# APM2_Adapter.net
KiCad netlist of a schematic drawn in EAGLE
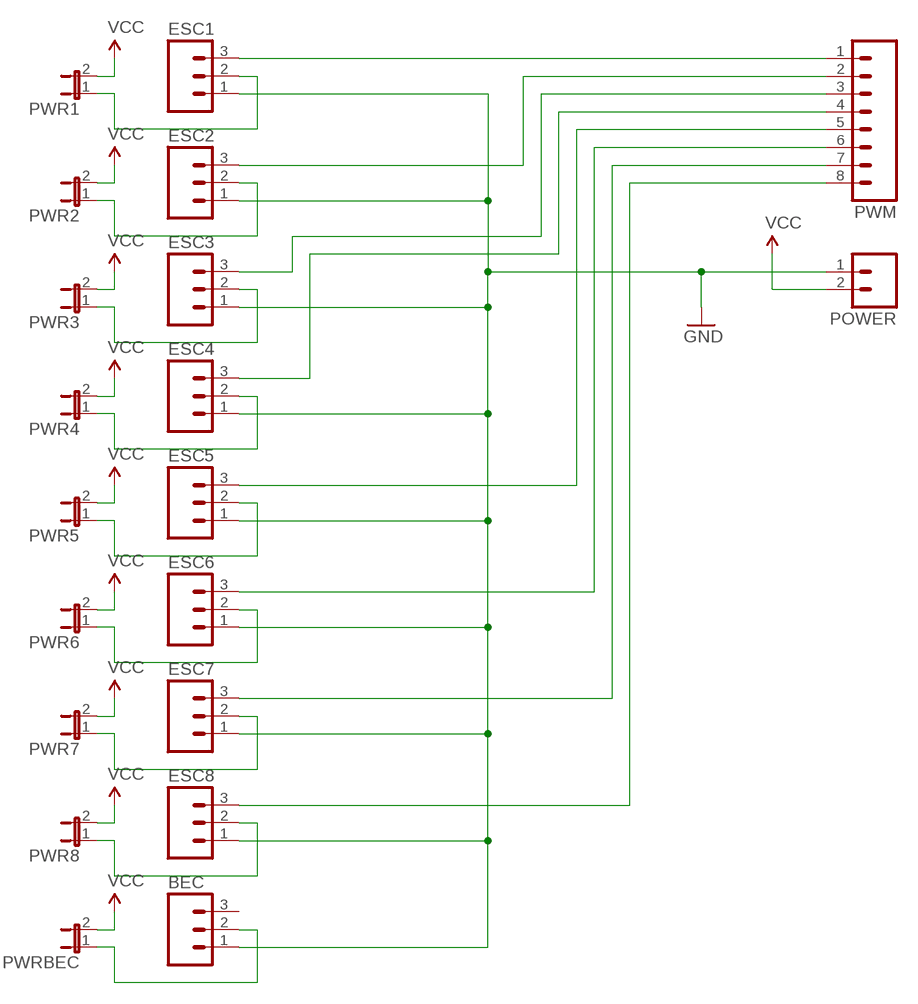
[diagram p0: schematic, sheet 1]

(export (version "E")
  (design (tool "Eeschema 10.0.6"))
  (components
    (comp (ref "BEC")
      (value "M03LOCK")
      (footprint "eagle-import:1X03_LOCK")
      (libsource (lib "eagle-import") (part "M03LOCK"))
    )
    (comp (ref "ESC1")
      (value "M03LOCK")
      (footprint "eagle-import:1X03_LOCK")
      (libsource (lib "eagle-import") (part "M03LOCK"))
    )
    (comp (ref "ESC2")
      (value "M03LOCK")
      (footprint "eagle-import:1X03_LOCK")
      (libsource (lib "eagle-import") (part "M03LOCK"))
    )
    (comp (ref "ESC3")
      (value "M03LOCK")
      (footprint "eagle-import:1X03_LOCK")
      (libsource (lib "eagle-import") (part "M03LOCK"))
    )
    (comp (ref "ESC4")
      (value "M03LOCK")
      (footprint "eagle-import:1X03_LOCK")
      (libsource (lib "eagle-import") (part "M03LOCK"))
    )
    (comp (ref "ESC5")
      (value "M03LOCK")
      (footprint "eagle-import:1X03_LOCK")
      (libsource (lib "eagle-import") (part "M03LOCK"))
    )
    (comp (ref "ESC6")
      (value "M03LOCK")
      (footprint "eagle-import:1X03_LOCK")
      (libsource (lib "eagle-import") (part "M03LOCK"))
    )
    (comp (ref "ESC7")
      (value "M03LOCK")
      (footprint "eagle-import:1X03_LOCK")
      (libsource (lib "eagle-import") (part "M03LOCK"))
    )
    (comp (ref "ESC8")
      (value "M03LOCK")
      (footprint "eagle-import:1X03_LOCK")
      (libsource (lib "eagle-import") (part "M03LOCK"))
    )
    (comp (ref "POWER")
      (value "M02LOCK")
      (footprint "eagle-import:1X02_LOCK")
      (libsource (lib "eagle-import") (part "M02LOCK"))
    )
    (comp (ref "PWM")
      (value "M08LOCK")
      (footprint "eagle-import:1X08_LOCK")
      (libsource (lib "eagle-import") (part "M08LOCK"))
    )
    (comp (ref "PWR1")
      (value "JUMPER-2PTH")
      (footprint "eagle-import:1X02")
      (libsource (lib "eagle-import") (part "JUMPER-2PTH"))
    )
    (comp (ref "PWR2")
      (value "JUMPER-2PTH")
      (footprint "eagle-import:1X02")
      (libsource (lib "eagle-import") (part "JUMPER-2PTH"))
    )
    (comp (ref "PWR3")
      (value "JUMPER-2PTH")
      (footprint "eagle-import:1X02")
      (libsource (lib "eagle-import") (part "JUMPER-2PTH"))
    )
    (comp (ref "PWR4")
      (value "JUMPER-2PTH")
      (footprint "eagle-import:1X02")
      (libsource (lib "eagle-import") (part "JUMPER-2PTH"))
    )
    (comp (ref "PWR5")
      (value "JUMPER-2PTH")
      (footprint "eagle-import:1X02")
      (libsource (lib "eagle-import") (part "JUMPER-2PTH"))
    )
    (comp (ref "PWR6")
      (value "JUMPER-2PTH")
      (footprint "eagle-import:1X02")
      (libsource (lib "eagle-import") (part "JUMPER-2PTH"))
    )
    (comp (ref "PWR7")
      (value "JUMPER-2PTH")
      (footprint "eagle-import:1X02")
      (libsource (lib "eagle-import") (part "JUMPER-2PTH"))
    )
    (comp (ref "PWR8")
      (value "JUMPER-2PTH")
      (footprint "eagle-import:1X02")
      (libsource (lib "eagle-import") (part "JUMPER-2PTH"))
    )
    (comp (ref "PWRBEC")
      (value "JUMPER-2PTH")
      (footprint "eagle-import:1X02")
      (libsource (lib "eagle-import") (part "JUMPER-2PTH"))
    )
  )
  (nets
    (net (code "1") (name "GND") (class "Default")
      (node (ref "BEC") (pin "1") (pinfunction "1_1") (pintype "passive"))
      (node (ref "ESC1") (pin "1") (pinfunction "1_1") (pintype "passive"))
      (node (ref "ESC2") (pin "1") (pinfunction "1_1") (pintype "passive"))
      (node (ref "ESC3") (pin "1") (pinfunction "1_1") (pintype "passive"))
      (node (ref "ESC4") (pin "1") (pinfunction "1_1") (pintype "passive"))
      (node (ref "ESC5") (pin "1") (pinfunction "1_1") (pintype "passive"))
      (node (ref "ESC6") (pin "1") (pinfunction "1_1") (pintype "passive"))
      (node (ref "ESC7") (pin "1") (pinfunction "1_1") (pintype "passive"))
      (node (ref "ESC8") (pin "1") (pinfunction "1_1") (pintype "passive"))
      (node (ref "POWER") (pin "1") (pinfunction "1_1") (pintype "passive"))
    )
    (net (code "2") (name "Net-(BEC-Pad2)") (class "Default")
      (node (ref "BEC") (pin "2") (pinfunction "2_2") (pintype "passive"))
      (node (ref "PWRBEC") (pin "1") (pinfunction "1_1") (pintype "passive"))
    )
    (net (code "3") (name "Net-(ESC1-Pad2)") (class "Default")
      (node (ref "ESC1") (pin "2") (pinfunction "2_2") (pintype "passive"))
      (node (ref "PWR1") (pin "1") (pinfunction "1_1") (pintype "passive"))
    )
    (net (code "4") (name "Net-(ESC1-Pad3)") (class "Default")
      (node (ref "ESC1") (pin "3") (pinfunction "3_3") (pintype "passive"))
      (node (ref "PWM") (pin "1") (pinfunction "1_1") (pintype "passive"))
    )
    (net (code "5") (name "Net-(ESC2-Pad2)") (class "Default")
      (node (ref "ESC2") (pin "2") (pinfunction "2_2") (pintype "passive"))
      (node (ref "PWR2") (pin "1") (pinfunction "1_1") (pintype "passive"))
    )
    (net (code "6") (name "Net-(ESC2-Pad3)") (class "Default")
      (node (ref "ESC2") (pin "3") (pinfunction "3_3") (pintype "passive"))
      (node (ref "PWM") (pin "2") (pinfunction "2_2") (pintype "passive"))
    )
    (net (code "7") (name "Net-(ESC3-Pad2)") (class "Default")
      (node (ref "ESC3") (pin "2") (pinfunction "2_2") (pintype "passive"))
      (node (ref "PWR3") (pin "1") (pinfunction "1_1") (pintype "passive"))
    )
    (net (code "8") (name "Net-(ESC3-Pad3)") (class "Default")
      (node (ref "ESC3") (pin "3") (pinfunction "3_3") (pintype "passive"))
      (node (ref "PWM") (pin "3") (pinfunction "3_3") (pintype "passive"))
    )
    (net (code "9") (name "Net-(ESC4-Pad2)") (class "Default")
      (node (ref "ESC4") (pin "2") (pinfunction "2_2") (pintype "passive"))
      (node (ref "PWR4") (pin "1") (pinfunction "1_1") (pintype "passive"))
    )
    (net (code "10") (name "Net-(ESC4-Pad3)") (class "Default")
      (node (ref "ESC4") (pin "3") (pinfunction "3_3") (pintype "passive"))
      (node (ref "PWM") (pin "4") (pinfunction "4_4") (pintype "passive"))
    )
    (net (code "11") (name "Net-(ESC5-Pad2)") (class "Default")
      (node (ref "ESC5") (pin "2") (pinfunction "2_2") (pintype "passive"))
      (node (ref "PWR5") (pin "1") (pinfunction "1_1") (pintype "passive"))
    )
    (net (code "12") (name "Net-(ESC5-Pad3)") (class "Default")
      (node (ref "ESC5") (pin "3") (pinfunction "3_3") (pintype "passive"))
      (node (ref "PWM") (pin "5") (pinfunction "5_5") (pintype "passive"))
    )
    (net (code "13") (name "Net-(ESC6-Pad2)") (class "Default")
      (node (ref "ESC6") (pin "2") (pinfunction "2_2") (pintype "passive"))
      (node (ref "PWR6") (pin "1") (pinfunction "1_1") (pintype "passive"))
    )
    (net (code "14") (name "Net-(ESC6-Pad3)") (class "Default")
      (node (ref "ESC6") (pin "3") (pinfunction "3_3") (pintype "passive"))
      (node (ref "PWM") (pin "6") (pinfunction "6_6") (pintype "passive"))
    )
    (net (code "15") (name "Net-(ESC7-Pad2)") (class "Default")
      (node (ref "ESC7") (pin "2") (pinfunction "2_2") (pintype "passive"))
      (node (ref "PWR7") (pin "1") (pinfunction "1_1") (pintype "passive"))
    )
    (net (code "16") (name "Net-(ESC7-Pad3)") (class "Default")
      (node (ref "ESC7") (pin "3") (pinfunction "3_3") (pintype "passive"))
      (node (ref "PWM") (pin "7") (pinfunction "7_7") (pintype "passive"))
    )
    (net (code "17") (name "Net-(ESC8-Pad2)") (class "Default")
      (node (ref "ESC8") (pin "2") (pinfunction "2_2") (pintype "passive"))
      (node (ref "PWR8") (pin "1") (pinfunction "1_1") (pintype "passive"))
    )
    (net (code "18") (name "Net-(ESC8-Pad3)") (class "Default")
      (node (ref "ESC8") (pin "3") (pinfunction "3_3") (pintype "passive"))
      (node (ref "PWM") (pin "8") (pinfunction "8_8") (pintype "passive"))
    )
    (net (code "19") (name "VCC") (class "Default")
      (node (ref "POWER") (pin "2") (pinfunction "2_2") (pintype "passive"))
      (node (ref "PWR1") (pin "2") (pinfunction "2_2") (pintype "passive"))
      (node (ref "PWR2") (pin "2") (pinfunction "2_2") (pintype "passive"))
      (node (ref "PWR3") (pin "2") (pinfunction "2_2") (pintype "passive"))
      (node (ref "PWR4") (pin "2") (pinfunction "2_2") (pintype "passive"))
      (node (ref "PWR5") (pin "2") (pinfunction "2_2") (pintype "passive"))
      (node (ref "PWR6") (pin "2") (pinfunction "2_2") (pintype "passive"))
      (node (ref "PWR7") (pin "2") (pinfunction "2_2") (pintype "passive"))
      (node (ref "PWR8") (pin "2") (pinfunction "2_2") (pintype "passive"))
      (node (ref "PWRBEC") (pin "2") (pinfunction "2_2") (pintype "passive"))
    )
    (net (code "20") (name "unconnected-(BEC-Pad3)") (class "Default")
      (node (ref "BEC") (pin "3") (pinfunction "3_3") (pintype "passive"))
    )
  )
)
